# switch_reed.net
KiCad netlist of a schematic drawn in EAGLE
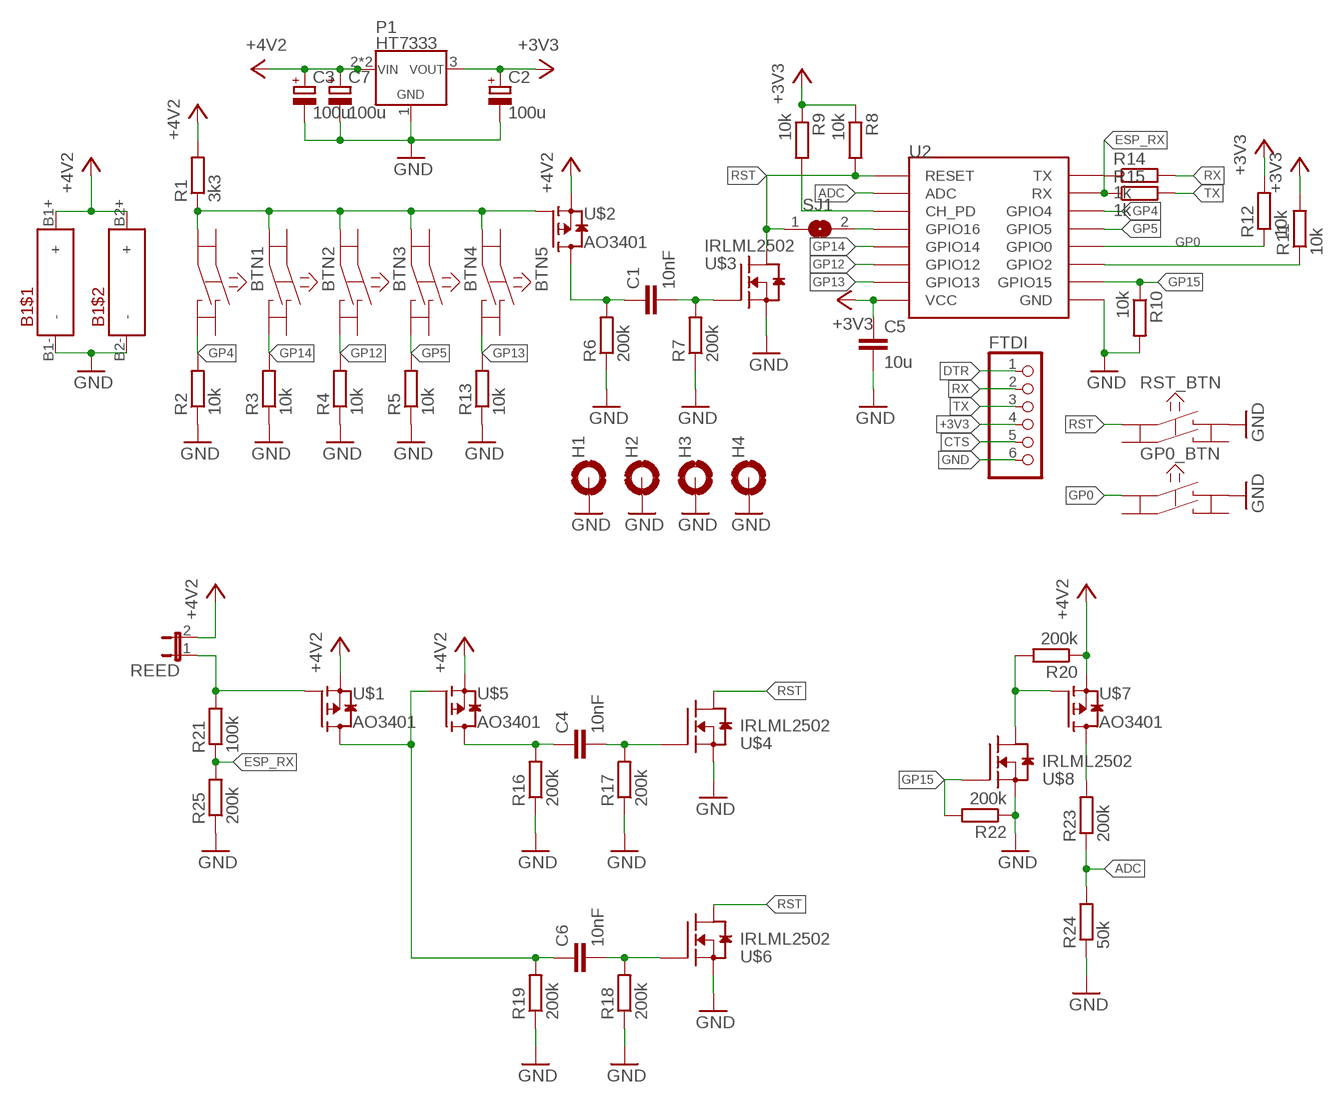
[diagram p0: schematic, sheet 1]

(export (version "E")
  (design (tool "Eeschema 10.0.6"))
  (components
    (comp (ref "B1")
      (value "18650_2X")
      (footprint "eagle-import:18650_HOLDER")
      (libsource (lib "eagle-import") (part "18650_2X"))
    )
    (comp (ref "BTN1")
      (value "KSM611A")
      (footprint "eagle-import:KSM611A")
      (libsource (lib "eagle-import") (part "KSM611A"))
    )
    (comp (ref "BTN2")
      (value "KSM611A")
      (footprint "eagle-import:KSM611A")
      (libsource (lib "eagle-import") (part "KSM611A"))
    )
    (comp (ref "BTN3")
      (value "KSM611A")
      (footprint "eagle-import:KSM611A")
      (libsource (lib "eagle-import") (part "KSM611A"))
    )
    (comp (ref "BTN4")
      (value "KSM611A")
      (footprint "eagle-import:KSM611A")
      (libsource (lib "eagle-import") (part "KSM611A"))
    )
    (comp (ref "BTN5")
      (value "KSM611A")
      (footprint "eagle-import:KSM611A")
      (libsource (lib "eagle-import") (part "KSM611A"))
    )
    (comp (ref "C1")
      (value "10nF")
      (footprint "eagle-import:C0805")
      (libsource (lib "eagle-import") (part "C-EUC0805"))
    )
    (comp (ref "C2")
      (value "100u")
      (footprint "eagle-import:E5-8,5")
      (libsource (lib "eagle-import") (part "CPOL-EUE5-8.5"))
    )
    (comp (ref "C3")
      (value "100u")
      (footprint "eagle-import:E5-8,5")
      (libsource (lib "eagle-import") (part "CPOL-EUE5-8.5"))
    )
    (comp (ref "C4")
      (value "10nF")
      (footprint "eagle-import:C0805")
      (libsource (lib "eagle-import") (part "C-EUC0805"))
    )
    (comp (ref "C5")
      (value "10u")
      (footprint "eagle-import:C1206")
      (libsource (lib "eagle-import") (part "C-EUC1206"))
    )
    (comp (ref "C6")
      (value "10nF")
      (footprint "eagle-import:C0805")
      (libsource (lib "eagle-import") (part "C-EUC0805"))
    )
    (comp (ref "C7")
      (value "100u")
      (footprint "eagle-import:E5-8,5")
      (libsource (lib "eagle-import") (part "CPOL-EUE5-8.5"))
    )
    (comp (ref "FTDI")
      (value "PINHD-1X06_2.54-S")
      (footprint "eagle-import:1X06-S")
      (libsource (lib "eagle-import") (part "PINHD-1X06_2.54-S"))
    )
    (comp (ref "GP0_BTN")
      (value "KSM611A")
      (footprint "eagle-import:KSM611A")
      (libsource (lib "eagle-import") (part "KSM611A"))
    )
    (comp (ref "H1")
      (value "MOUNT-PAD-ROUND3.2")
      (footprint "eagle-import:3,2-PAD")
      (libsource (lib "eagle-import") (part "MOUNT-PAD-ROUND3.2"))
    )
    (comp (ref "H2")
      (value "MOUNT-PAD-ROUND3.2")
      (footprint "eagle-import:3,2-PAD")
      (libsource (lib "eagle-import") (part "MOUNT-PAD-ROUND3.2"))
    )
    (comp (ref "H3")
      (value "MOUNT-PAD-ROUND3.2")
      (footprint "eagle-import:3,2-PAD")
      (libsource (lib "eagle-import") (part "MOUNT-PAD-ROUND3.2"))
    )
    (comp (ref "H4")
      (value "MOUNT-PAD-ROUND3.2")
      (footprint "eagle-import:3,2-PAD")
      (libsource (lib "eagle-import") (part "MOUNT-PAD-ROUND3.2"))
    )
    (comp (ref "P1")
      (value "HT7333")
      (footprint "eagle-import:SOT89")
      (libsource (lib "eagle-import") (part "HT7333SOT89"))
    )
    (comp (ref "R1")
      (value "3k3")
      (footprint "eagle-import:R0805")
      (libsource (lib "eagle-import") (part "R-EU_R0805"))
    )
    (comp (ref "R2")
      (value "10k")
      (footprint "eagle-import:R0805")
      (libsource (lib "eagle-import") (part "R-EU_R0805"))
    )
    (comp (ref "R3")
      (value "10k")
      (footprint "eagle-import:R0805")
      (libsource (lib "eagle-import") (part "R-EU_R0805"))
    )
    (comp (ref "R4")
      (value "10k")
      (footprint "eagle-import:R0805")
      (libsource (lib "eagle-import") (part "R-EU_R0805"))
    )
    (comp (ref "R5")
      (value "10k")
      (footprint "eagle-import:R0805")
      (libsource (lib "eagle-import") (part "R-EU_R0805"))
    )
    (comp (ref "R6")
      (value "200k")
      (footprint "eagle-import:R0805")
      (libsource (lib "eagle-import") (part "R-EU_R0805"))
    )
    (comp (ref "R7")
      (value "200k")
      (footprint "eagle-import:R0805")
      (libsource (lib "eagle-import") (part "R-EU_R0805"))
    )
    (comp (ref "R8")
      (value "10k")
      (footprint "eagle-import:R0805")
      (libsource (lib "eagle-import") (part "R-EU_R0805"))
    )
    (comp (ref "R9")
      (value "10k")
      (footprint "eagle-import:R0805")
      (libsource (lib "eagle-import") (part "R-EU_R0805"))
    )
    (comp (ref "R10")
      (value "10k")
      (footprint "eagle-import:R0805")
      (libsource (lib "eagle-import") (part "R-EU_R0805"))
    )
    (comp (ref "R11")
      (value "10k")
      (footprint "eagle-import:R0805")
      (libsource (lib "eagle-import") (part "R-EU_R0805"))
    )
    (comp (ref "R12")
      (value "10k")
      (footprint "eagle-import:R0805")
      (libsource (lib "eagle-import") (part "R-EU_R0805"))
    )
    (comp (ref "R13")
      (value "10k")
      (footprint "eagle-import:R0805")
      (libsource (lib "eagle-import") (part "R-EU_R0805"))
    )
    (comp (ref "R14")
      (value "1k")
      (footprint "eagle-import:R0805")
      (libsource (lib "eagle-import") (part "R-EU_R0805"))
    )
    (comp (ref "R15")
      (value "1k")
      (footprint "eagle-import:R0805")
      (libsource (lib "eagle-import") (part "R-EU_R0805"))
    )
    (comp (ref "R16")
      (value "200k")
      (footprint "eagle-import:R0805")
      (libsource (lib "eagle-import") (part "R-EU_R0805"))
    )
    (comp (ref "R17")
      (value "200k")
      (footprint "eagle-import:R0805")
      (libsource (lib "eagle-import") (part "R-EU_R0805"))
    )
    (comp (ref "R18")
      (value "200k")
      (footprint "eagle-import:R0805")
      (libsource (lib "eagle-import") (part "R-EU_R0805"))
    )
    (comp (ref "R19")
      (value "200k")
      (footprint "eagle-import:R0805")
      (libsource (lib "eagle-import") (part "R-EU_R0805"))
    )
    (comp (ref "R20")
      (value "200k")
      (footprint "eagle-import:R0805")
      (libsource (lib "eagle-import") (part "R-EU_R0805"))
    )
    (comp (ref "R21")
      (value "100k")
      (footprint "eagle-import:R0805")
      (libsource (lib "eagle-import") (part "R-EU_R0805"))
    )
    (comp (ref "R22")
      (value "200k")
      (footprint "eagle-import:R0805")
      (libsource (lib "eagle-import") (part "R-EU_R0805"))
    )
    (comp (ref "R23")
      (value "200k")
      (footprint "eagle-import:R0805")
      (libsource (lib "eagle-import") (part "R-EU_R0805"))
    )
    (comp (ref "R24")
      (value "50k")
      (footprint "eagle-import:R0805")
      (libsource (lib "eagle-import") (part "R-EU_R0805"))
    )
    (comp (ref "R25")
      (value "200k")
      (footprint "eagle-import:R0805")
      (libsource (lib "eagle-import") (part "R-EU_R0805"))
    )
    (comp (ref "REED")
      (value "JP1E")
      (footprint "eagle-import:JP1")
      (libsource (lib "eagle-import") (part "JP1E"))
    )
    (comp (ref "RST_BTN")
      (value "KSM611A")
      (footprint "eagle-import:KSM611A")
      (libsource (lib "eagle-import") (part "KSM611A"))
    )
    (comp (ref "SJ1") (value "SJ") (footprint "eagle-import:SJ") (libsource (lib "eagle-import") (part "SJ")))
    (comp (ref "U$1")
      (value "AO3401")
      (footprint "eagle-import:SOT23")
      (libsource (lib "eagle-import") (part "P-CH_AO3401"))
    )
    (comp (ref "U$2")
      (value "AO3401")
      (footprint "eagle-import:SOT23")
      (libsource (lib "eagle-import") (part "P-CH_AO3401"))
    )
    (comp (ref "U$3")
      (value "IRLML2502")
      (footprint "eagle-import:SOT23")
      (libsource (lib "eagle-import") (part "N-CH_IRLML2502"))
    )
    (comp (ref "U$4")
      (value "IRLML2502")
      (footprint "eagle-import:SOT23")
      (libsource (lib "eagle-import") (part "N-CH_IRLML2502"))
    )
    (comp (ref "U$5")
      (value "AO3401")
      (footprint "eagle-import:SOT23")
      (libsource (lib "eagle-import") (part "P-CH_AO3401"))
    )
    (comp (ref "U$6")
      (value "IRLML2502")
      (footprint "eagle-import:SOT23")
      (libsource (lib "eagle-import") (part "N-CH_IRLML2502"))
    )
    (comp (ref "U$7")
      (value "AO3401")
      (footprint "eagle-import:SOT23")
      (libsource (lib "eagle-import") (part "P-CH_AO3401"))
    )
    (comp (ref "U$8")
      (value "IRLML2502")
      (footprint "eagle-import:SOT23")
      (libsource (lib "eagle-import") (part "N-CH_IRLML2502"))
    )
    (comp (ref "U2")
      (value "ESP12SMD")
      (footprint "eagle-import:ESP12-SMD")
      (libsource (lib "eagle-import") (part "ESP12SMD"))
    )
  )
  (nets
    (net (code "1") (name "+3V3") (class "Default")
      (node (ref "C2") (pin "+") (pinfunction "+_+") (pintype "passive"))
      (node (ref "C5") (pin "1") (pinfunction "1_1") (pintype "passive"))
      (node (ref "FTDI") (pin "4") (pinfunction "4_4") (pintype "passive"))
      (node (ref "P1") (pin "3") (pinfunction "VOUT_3") (pintype "power_in"))
      (node (ref "R11") (pin "2") (pinfunction "2_2") (pintype "passive"))
      (node (ref "R12") (pin "2") (pinfunction "2_2") (pintype "passive"))
      (node (ref "R8") (pin "1") (pinfunction "1_1") (pintype "passive"))
      (node (ref "R9") (pin "1") (pinfunction "1_1") (pintype "passive"))
      (node (ref "U2") (pin "VCC") (pinfunction "VCC_VCC") (pintype "bidirectional"))
    )
    (net (code "2") (name "+4V2") (class "Default")
      (node (ref "B1") (pin "B1+") (pinfunction "+_B1+") (pintype "power_in"))
      (node (ref "B1") (pin "B2+") (pinfunction "+_B2+") (pintype "power_in"))
      (node (ref "C3") (pin "+") (pinfunction "+_+") (pintype "passive"))
      (node (ref "C7") (pin "+") (pinfunction "+_+") (pintype "passive"))
      (node (ref "P1") (pin "2") (pinfunction "VIN_2") (pintype "power_in"))
      (node (ref "P1") (pin "2@1") (pinfunction "VIN_2@1") (pintype "power_in"))
      (node (ref "R1") (pin "2") (pinfunction "2_2") (pintype "passive"))
      (node (ref "R20") (pin "1") (pinfunction "1_1") (pintype "passive"))
      (node (ref "REED") (pin "2") (pinfunction "2_2") (pintype "passive"))
      (node (ref "U$1") (pin "2") (pinfunction "S_2") (pintype "passive"))
      (node (ref "U$2") (pin "2") (pinfunction "S_2") (pintype "passive"))
      (node (ref "U$5") (pin "2") (pinfunction "S_2") (pintype "passive"))
      (node (ref "U$7") (pin "2") (pinfunction "S_2") (pintype "passive"))
    )
    (net (code "3") (name "ADC") (class "Default")
      (node (ref "R23") (pin "1") (pinfunction "1_1") (pintype "passive"))
      (node (ref "R24") (pin "2") (pinfunction "2_2") (pintype "passive"))
      (node (ref "U2") (pin "ADC") (pinfunction "ADC_ADC") (pintype "bidirectional"))
    )
    (net (code "4") (name "CTS") (class "Default")
      (node (ref "FTDI") (pin "5") (pinfunction "5_5") (pintype "passive"))
    )
    (net (code "5") (name "DTR") (class "Default")
      (node (ref "FTDI") (pin "1") (pinfunction "1_1") (pintype "passive"))
    )
    (net (code "6") (name "ESP_RX") (class "Default")
      (node (ref "R15") (pin "1") (pinfunction "1_1") (pintype "passive"))
      (node (ref "R21") (pin "1") (pinfunction "1_1") (pintype "passive"))
      (node (ref "R25") (pin "2") (pinfunction "2_2") (pintype "passive"))
      (node (ref "U2") (pin "RXD0") (pinfunction "RX_RXD0") (pintype "bidirectional"))
    )
    (net (code "7") (name "GND") (class "Default")
      (node (ref "B1") (pin "B1-") (pinfunction "-_B1-") (pintype "power_in"))
      (node (ref "B1") (pin "B2-") (pinfunction "-_B2-") (pintype "power_in"))
      (node (ref "C2") (pin "-") (pinfunction "-_-") (pintype "passive"))
      (node (ref "C3") (pin "-") (pinfunction "-_-") (pintype "passive"))
      (node (ref "C5") (pin "2") (pinfunction "2_2") (pintype "passive"))
      (node (ref "C7") (pin "-") (pinfunction "-_-") (pintype "passive"))
      (node (ref "FTDI") (pin "6") (pinfunction "6_6") (pintype "passive"))
      (node (ref "GP0_BTN") (pin "B") (pinfunction "B_B") (pintype "passive"))
      (node (ref "H1") (pin "B3,2") (pinfunction "MOUNT_B3,2") (pintype "passive"))
      (node (ref "H2") (pin "B3,2") (pinfunction "MOUNT_B3,2") (pintype "passive"))
      (node (ref "H3") (pin "B3,2") (pinfunction "MOUNT_B3,2") (pintype "passive"))
      (node (ref "H4") (pin "B3,2") (pinfunction "MOUNT_B3,2") (pintype "passive"))
      (node (ref "P1") (pin "1") (pinfunction "GND_1") (pintype "power_in"))
      (node (ref "R10") (pin "2") (pinfunction "2_2") (pintype "passive"))
      (node (ref "R13") (pin "1") (pinfunction "1_1") (pintype "passive"))
      (node (ref "R16") (pin "1") (pinfunction "1_1") (pintype "passive"))
      (node (ref "R17") (pin "1") (pinfunction "1_1") (pintype "passive"))
      (node (ref "R18") (pin "1") (pinfunction "1_1") (pintype "passive"))
      (node (ref "R19") (pin "1") (pinfunction "1_1") (pintype "passive"))
      (node (ref "R2") (pin "1") (pinfunction "1_1") (pintype "passive"))
      (node (ref "R22") (pin "1") (pinfunction "1_1") (pintype "passive"))
      (node (ref "R24") (pin "1") (pinfunction "1_1") (pintype "passive"))
      (node (ref "R25") (pin "1") (pinfunction "1_1") (pintype "passive"))
      (node (ref "R3") (pin "1") (pinfunction "1_1") (pintype "passive"))
      (node (ref "R4") (pin "1") (pinfunction "1_1") (pintype "passive"))
      (node (ref "R5") (pin "1") (pinfunction "1_1") (pintype "passive"))
      (node (ref "R6") (pin "1") (pinfunction "1_1") (pintype "passive"))
      (node (ref "R7") (pin "1") (pinfunction "1_1") (pintype "passive"))
      (node (ref "RST_BTN") (pin "B") (pinfunction "B_B") (pintype "passive"))
      (node (ref "U$3") (pin "2") (pinfunction "S_2") (pintype "passive"))
      (node (ref "U$4") (pin "2") (pinfunction "S_2") (pintype "passive"))
      (node (ref "U$6") (pin "2") (pinfunction "S_2") (pintype "passive"))
      (node (ref "U$8") (pin "2") (pinfunction "S_2") (pintype "passive"))
      (node (ref "U2") (pin "GND") (pinfunction "GND_GND") (pintype "bidirectional"))
    )
    (net (code "8") (name "GP0") (class "Default")
      (node (ref "GP0_BTN") (pin "A") (pinfunction "A_A") (pintype "passive"))
      (node (ref "R12") (pin "1") (pinfunction "1_1") (pintype "passive"))
      (node (ref "U2") (pin "GPIO0") (pinfunction "GPIO0_GPIO0") (pintype "bidirectional"))
    )
    (net (code "9") (name "GP4") (class "Default")
      (node (ref "BTN1") (pin "D") (pinfunction "D_D") (pintype "passive"))
      (node (ref "R2") (pin "2") (pinfunction "2_2") (pintype "passive"))
      (node (ref "U2") (pin "GPIO4") (pinfunction "GPIO4_GPIO4") (pintype "bidirectional"))
    )
    (net (code "10") (name "GP5") (class "Default")
      (node (ref "BTN4") (pin "D") (pinfunction "D_D") (pintype "passive"))
      (node (ref "R5") (pin "2") (pinfunction "2_2") (pintype "passive"))
      (node (ref "U2") (pin "GPIO5") (pinfunction "GPIO5_GPIO5") (pintype "bidirectional"))
    )
    (net (code "11") (name "GP12") (class "Default")
      (node (ref "BTN3") (pin "D") (pinfunction "D_D") (pintype "passive"))
      (node (ref "R4") (pin "2") (pinfunction "2_2") (pintype "passive"))
      (node (ref "U2") (pin "GPIO12") (pinfunction "GPIO12_GPIO12") (pintype "bidirectional"))
    )
    (net (code "12") (name "GP13") (class "Default")
      (node (ref "BTN5") (pin "D") (pinfunction "D_D") (pintype "passive"))
      (node (ref "R13") (pin "2") (pinfunction "2_2") (pintype "passive"))
      (node (ref "U2") (pin "GPIO13") (pinfunction "GPIO13_GPIO13") (pintype "bidirectional"))
    )
    (net (code "13") (name "GP14") (class "Default")
      (node (ref "BTN2") (pin "D") (pinfunction "D_D") (pintype "passive"))
      (node (ref "R3") (pin "2") (pinfunction "2_2") (pintype "passive"))
      (node (ref "U2") (pin "GPIO14") (pinfunction "GPIO14_GPIO14") (pintype "bidirectional"))
    )
    (net (code "14") (name "GP15") (class "Default")
      (node (ref "R10") (pin "1") (pinfunction "1_1") (pintype "passive"))
      (node (ref "R22") (pin "2") (pinfunction "2_2") (pintype "passive"))
      (node (ref "U$8") (pin "1") (pinfunction "G_1") (pintype "passive"))
      (node (ref "U2") (pin "GPIO15") (pinfunction "GPIO15_GPIO15") (pintype "bidirectional"))
    )
    (net (code "15") (name "Net-(R9-Pad2)") (class "Default")
      (node (ref "R9") (pin "2") (pinfunction "2_2") (pintype "passive"))
      (node (ref "U2") (pin "CH_PD") (pinfunction "CH_PD_CH_PD") (pintype "bidirectional"))
    )
    (net (code "16") (name "Net-(R11-Pad1)") (class "Default")
      (node (ref "R11") (pin "1") (pinfunction "1_1") (pintype "passive"))
      (node (ref "U2") (pin "GPIO2") (pinfunction "GPIO2_GPIO2") (pintype "bidirectional"))
    )
    (net (code "17") (name "Net-(SJ1-Pad2)") (class "Default")
      (node (ref "SJ1") (pin "2") (pinfunction "2_2") (pintype "passive"))
      (node (ref "U2") (pin "GPIO16") (pinfunction "GPIO16_GPIO16") (pintype "bidirectional"))
    )
    (net (code "18") (name "Net-(U$1-D)") (class "Default")
      (node (ref "C6") (pin "1") (pinfunction "1_1") (pintype "passive"))
      (node (ref "R19") (pin "2") (pinfunction "2_2") (pintype "passive"))
      (node (ref "U$1") (pin "3") (pinfunction "D_3") (pintype "passive"))
      (node (ref "U$5") (pin "1") (pinfunction "G_1") (pintype "passive"))
    )
    (net (code "19") (name "Net-(U$1-G)") (class "Default")
      (node (ref "R21") (pin "2") (pinfunction "2_2") (pintype "passive"))
      (node (ref "REED") (pin "1") (pinfunction "1_1") (pintype "passive"))
      (node (ref "U$1") (pin "1") (pinfunction "G_1") (pintype "passive"))
    )
    (net (code "20") (name "Net-(U$2-D)") (class "Default")
      (node (ref "C1") (pin "1") (pinfunction "1_1") (pintype "passive"))
      (node (ref "R6") (pin "2") (pinfunction "2_2") (pintype "passive"))
      (node (ref "U$2") (pin "3") (pinfunction "D_3") (pintype "passive"))
    )
    (net (code "21") (name "Net-(U$2-G)") (class "Default")
      (node (ref "BTN1") (pin "C") (pinfunction "C_C") (pintype "passive"))
      (node (ref "BTN2") (pin "C") (pinfunction "C_C") (pintype "passive"))
      (node (ref "BTN3") (pin "C") (pinfunction "C_C") (pintype "passive"))
      (node (ref "BTN4") (pin "C") (pinfunction "C_C") (pintype "passive"))
      (node (ref "BTN5") (pin "C") (pinfunction "C_C") (pintype "passive"))
      (node (ref "R1") (pin "1") (pinfunction "1_1") (pintype "passive"))
      (node (ref "U$2") (pin "1") (pinfunction "G_1") (pintype "passive"))
    )
    (net (code "22") (name "Net-(U$3-G)") (class "Default")
      (node (ref "C1") (pin "2") (pinfunction "2_2") (pintype "passive"))
      (node (ref "R7") (pin "2") (pinfunction "2_2") (pintype "passive"))
      (node (ref "U$3") (pin "1") (pinfunction "G_1") (pintype "passive"))
    )
    (net (code "23") (name "Net-(U$4-G)") (class "Default")
      (node (ref "C4") (pin "2") (pinfunction "2_2") (pintype "passive"))
      (node (ref "R17") (pin "2") (pinfunction "2_2") (pintype "passive"))
      (node (ref "U$4") (pin "1") (pinfunction "G_1") (pintype "passive"))
    )
    (net (code "24") (name "Net-(U$5-D)") (class "Default")
      (node (ref "C4") (pin "1") (pinfunction "1_1") (pintype "passive"))
      (node (ref "R16") (pin "2") (pinfunction "2_2") (pintype "passive"))
      (node (ref "U$5") (pin "3") (pinfunction "D_3") (pintype "passive"))
    )
    (net (code "25") (name "Net-(U$6-G)") (class "Default")
      (node (ref "C6") (pin "2") (pinfunction "2_2") (pintype "passive"))
      (node (ref "R18") (pin "2") (pinfunction "2_2") (pintype "passive"))
      (node (ref "U$6") (pin "1") (pinfunction "G_1") (pintype "passive"))
    )
    (net (code "26") (name "Net-(U$7-D)") (class "Default")
      (node (ref "R23") (pin "2") (pinfunction "2_2") (pintype "passive"))
      (node (ref "U$7") (pin "3") (pinfunction "D_3") (pintype "passive"))
    )
    (net (code "27") (name "Net-(U$7-G)") (class "Default")
      (node (ref "R20") (pin "2") (pinfunction "2_2") (pintype "passive"))
      (node (ref "U$7") (pin "1") (pinfunction "G_1") (pintype "passive"))
      (node (ref "U$8") (pin "3") (pinfunction "D_3") (pintype "passive"))
    )
    (net (code "28") (name "Net-(U2-TX)") (class "Default")
      (node (ref "R14") (pin "1") (pinfunction "1_1") (pintype "passive"))
      (node (ref "U2") (pin "TXD0") (pinfunction "TX_TXD0") (pintype "bidirectional"))
    )
    (net (code "29") (name "RST") (class "Default")
      (node (ref "R8") (pin "2") (pinfunction "2_2") (pintype "passive"))
      (node (ref "RST_BTN") (pin "A") (pinfunction "A_A") (pintype "passive"))
      (node (ref "SJ1") (pin "1") (pinfunction "1_1") (pintype "passive"))
      (node (ref "U$3") (pin "3") (pinfunction "D_3") (pintype "passive"))
      (node (ref "U$4") (pin "3") (pinfunction "D_3") (pintype "passive"))
      (node (ref "U$6") (pin "3") (pinfunction "D_3") (pintype "passive"))
      (node (ref "U2") (pin "RESET") (pinfunction "RESET_RESET") (pintype "bidirectional"))
    )
    (net (code "30") (name "RX") (class "Default")
      (node (ref "FTDI") (pin "2") (pinfunction "2_2") (pintype "passive"))
      (node (ref "R14") (pin "2") (pinfunction "2_2") (pintype "passive"))
    )
    (net (code "31") (name "TX") (class "Default")
      (node (ref "FTDI") (pin "3") (pinfunction "3_3") (pintype "passive"))
      (node (ref "R15") (pin "2") (pinfunction "2_2") (pintype "passive"))
    )
    (net (code "32") (name "unconnected-(BTN1-PadA)") (class "Default")
      (node (ref "BTN1") (pin "A") (pinfunction "A_A") (pintype "passive"))
    )
    (net (code "33") (name "unconnected-(BTN1-PadB)") (class "Default")
      (node (ref "BTN1") (pin "B") (pinfunction "B_B") (pintype "passive"))
    )
    (net (code "34") (name "unconnected-(BTN2-PadA)") (class "Default")
      (node (ref "BTN2") (pin "A") (pinfunction "A_A") (pintype "passive"))
    )
    (net (code "35") (name "unconnected-(BTN2-PadB)") (class "Default")
      (node (ref "BTN2") (pin "B") (pinfunction "B_B") (pintype "passive"))
    )
    (net (code "36") (name "unconnected-(BTN3-PadA)") (class "Default")
      (node (ref "BTN3") (pin "A") (pinfunction "A_A") (pintype "passive"))
    )
    (net (code "37") (name "unconnected-(BTN3-PadB)") (class "Default")
      (node (ref "BTN3") (pin "B") (pinfunction "B_B") (pintype "passive"))
    )
    (net (code "38") (name "unconnected-(BTN4-PadA)") (class "Default")
      (node (ref "BTN4") (pin "A") (pinfunction "A_A") (pintype "passive"))
    )
    (net (code "39") (name "unconnected-(BTN4-PadB)") (class "Default")
      (node (ref "BTN4") (pin "B") (pinfunction "B_B") (pintype "passive"))
    )
    (net (code "40") (name "unconnected-(BTN5-PadA)") (class "Default")
      (node (ref "BTN5") (pin "A") (pinfunction "A_A") (pintype "passive"))
    )
    (net (code "41") (name "unconnected-(BTN5-PadB)") (class "Default")
      (node (ref "BTN5") (pin "B") (pinfunction "B_B") (pintype "passive"))
    )
    (net (code "42") (name "unconnected-(GP0_BTN-PadC)") (class "Default")
      (node (ref "GP0_BTN") (pin "C") (pinfunction "C_C") (pintype "passive"))
    )
    (net (code "43") (name "unconnected-(GP0_BTN-PadD)") (class "Default")
      (node (ref "GP0_BTN") (pin "D") (pinfunction "D_D") (pintype "passive"))
    )
    (net (code "44") (name "unconnected-(RST_BTN-PadC)") (class "Default")
      (node (ref "RST_BTN") (pin "C") (pinfunction "C_C") (pintype "passive"))
    )
    (net (code "45") (name "unconnected-(RST_BTN-PadD)") (class "Default")
      (node (ref "RST_BTN") (pin "D") (pinfunction "D_D") (pintype "passive"))
    )
  )
)
